# eagle_exp_2.net
KiCad netlist of a schematic drawn in EAGLE
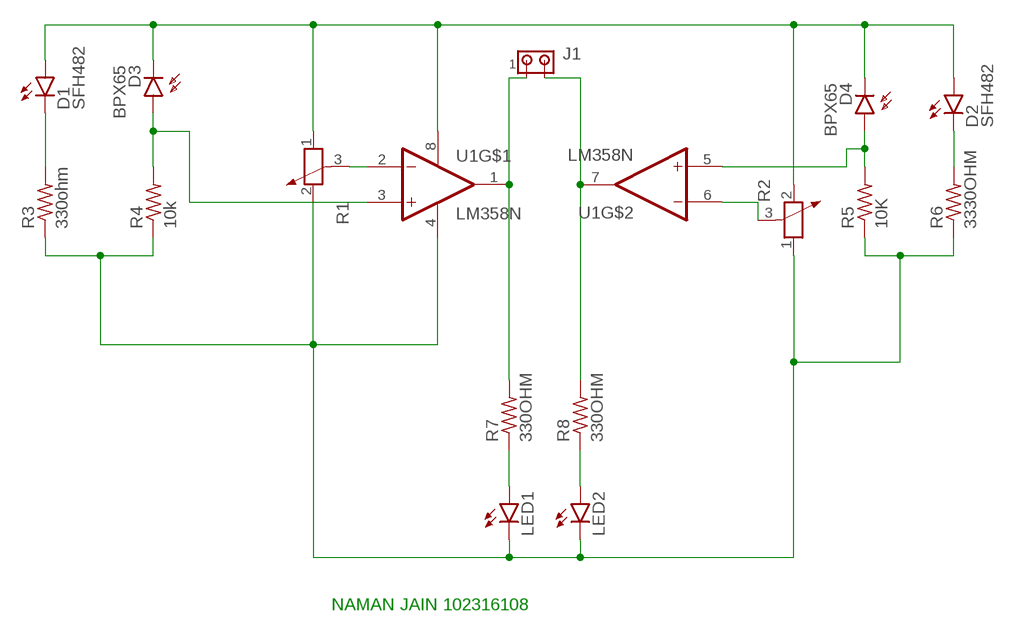
[diagram p0: schematic, sheet 1]

(export (version "E")
  (design (tool "Eeschema 10.0.6"))
  (components
    (comp (ref "D1")
      (value "SFH482")
      (footprint "eagle-import:SFH482")
      (libsource (lib "eagle-import") (part "SFH482"))
    )
    (comp (ref "D2")
      (value "SFH482")
      (footprint "eagle-import:SFH482")
      (libsource (lib "eagle-import") (part "SFH482"))
    )
    (comp (ref "D3")
      (value "BPX65")
      (footprint "eagle-import:BPX65")
      (fields (field (name "MPN") "BPX65."))
      (libsource (lib "eagle-import") (part "BPX65"))
    )
    (comp (ref "D4")
      (value "BPX65")
      (footprint "eagle-import:BPX65")
      (fields (field (name "MPN") "BPX65."))
      (libsource (lib "eagle-import") (part "BPX65"))
    )
    (comp (ref "J1")
      (value "MTA02-100")
      (footprint "eagle-import:10X02MTA")
      (libsource (lib "eagle-import") (part "MTA02-100"))
    )
    (comp (ref "LED1")
      (value "LED3MM")
      (footprint "eagle-import:LED3MM")
      (libsource (lib "eagle-import") (part "LED3MM"))
    )
    (comp (ref "LED2")
      (value "LED3MM")
      (footprint "eagle-import:LED3MM")
      (libsource (lib "eagle-import") (part "LED3MM"))
    )
    (comp (ref "R1")
      (value "POTENTIOMETER_PT-10")
      (footprint "eagle-import:PT-10")
      (libsource (lib "eagle-import") (part "POTENTIOMETER_PT-10"))
    )
    (comp (ref "R2")
      (value "POTENTIOMETER_PT-10")
      (footprint "eagle-import:PT-10")
      (libsource (lib "eagle-import") (part "POTENTIOMETER_PT-10"))
    )
    (comp (ref "R3")
      (value "330ohm")
      (footprint "eagle-import:0204_5")
      (libsource (lib "eagle-import") (part "R-US_0204/5"))
    )
    (comp (ref "R4")
      (value "10k")
      (footprint "eagle-import:0204_5")
      (libsource (lib "eagle-import") (part "R-US_0204/5"))
    )
    (comp (ref "R5")
      (value "10K")
      (footprint "eagle-import:0204_5")
      (libsource (lib "eagle-import") (part "R-US_0204/5"))
    )
    (comp (ref "R6")
      (value "3330OHM")
      (footprint "eagle-import:0204_5")
      (libsource (lib "eagle-import") (part "R-US_0204/5"))
    )
    (comp (ref "R7")
      (value "330OHM")
      (footprint "eagle-import:0204_5")
      (libsource (lib "eagle-import") (part "R-US_0204/5"))
    )
    (comp (ref "R8")
      (value "330OHM")
      (footprint "eagle-import:0204_5")
      (libsource (lib "eagle-import") (part "R-US_0204/5"))
    )
    (comp (ref "U1")
      (value "LM358N")
      (footprint "eagle-import:DIP762W46P254L960H508Q8")
      (fields (field (name "MF") "Harris Corporation"))
      (libsource (lib "eagle-import") (part "LM358N"))
    )
  )
  (nets
    (net (code "1") (name "Net-(D1-C)") (class "Default")
      (node (ref "D1") (pin "K") (pinfunction "C_K") (pintype "passive"))
      (node (ref "R3") (pin "2") (pinfunction "2_2") (pintype "passive"))
    )
    (net (code "2") (name "Net-(D2-C)") (class "Default")
      (node (ref "D2") (pin "K") (pinfunction "C_K") (pintype "passive"))
      (node (ref "R6") (pin "2") (pinfunction "2_2") (pintype "passive"))
    )
    (net (code "3") (name "Net-(D3-C)") (class "Default")
      (node (ref "D1") (pin "A") (pinfunction "A_A") (pintype "passive"))
      (node (ref "D2") (pin "A") (pinfunction "A_A") (pintype "passive"))
      (node (ref "D3") (pin "K") (pinfunction "C_K") (pintype "passive"))
      (node (ref "D4") (pin "K") (pinfunction "C_K") (pintype "passive"))
      (node (ref "R1") (pin "1") (pinfunction "1_1") (pintype "passive"))
      (node (ref "R2") (pin "2") (pinfunction "2_2") (pintype "passive"))
      (node (ref "U1") (pin "8") (pinfunction "VCC_8") (pintype "power_in"))
    )
    (net (code "4") (name "Net-(LED1-C)") (class "Default")
      (node (ref "LED1") (pin "K") (pinfunction "C_K") (pintype "passive"))
      (node (ref "LED2") (pin "K") (pinfunction "C_K") (pintype "passive"))
      (node (ref "R1") (pin "2") (pinfunction "2_2") (pintype "passive"))
      (node (ref "R2") (pin "1") (pinfunction "1_1") (pintype "passive"))
      (node (ref "R3") (pin "1") (pinfunction "1_1") (pintype "passive"))
      (node (ref "R4") (pin "1") (pinfunction "1_1") (pintype "passive"))
      (node (ref "R5") (pin "1") (pinfunction "1_1") (pintype "passive"))
      (node (ref "R6") (pin "1") (pinfunction "1_1") (pintype "passive"))
      (node (ref "U1") (pin "4") (pinfunction "GND_4") (pintype "power_in"))
    )
    (net (code "5") (name "Net-(LED1-PadA)") (class "Default")
      (node (ref "LED1") (pin "A") (pinfunction "A_A") (pintype "passive"))
      (node (ref "R7") (pin "1") (pinfunction "1_1") (pintype "passive"))
    )
    (net (code "6") (name "Net-(LED2-PadA)") (class "Default")
      (node (ref "LED2") (pin "A") (pinfunction "A_A") (pintype "passive"))
      (node (ref "R8") (pin "1") (pinfunction "1_1") (pintype "passive"))
    )
    (net (code "7") (name "Net-(U1A-1IN+)") (class "Default")
      (node (ref "D3") (pin "A") (pinfunction "A_A") (pintype "passive"))
      (node (ref "R4") (pin "2") (pinfunction "2_2") (pintype "passive"))
      (node (ref "U1") (pin "3") (pinfunction "1IN+_3") (pintype "input"))
    )
    (net (code "8") (name "Net-(U1A-1IN-)") (class "Default")
      (node (ref "R1") (pin "3") (pinfunction "3_3") (pintype "passive"))
      (node (ref "U1") (pin "2") (pinfunction "1IN-_2") (pintype "input"))
    )
    (net (code "9") (name "Net-(U1A-1OUT)") (class "Default")
      (node (ref "J1") (pin "1") (pinfunction "1_1") (pintype "passive"))
      (node (ref "R7") (pin "2") (pinfunction "2_2") (pintype "passive"))
      (node (ref "U1") (pin "1") (pinfunction "1OUT_1") (pintype "output"))
    )
    (net (code "10") (name "Net-(U1B-2IN+)") (class "Default")
      (node (ref "D4") (pin "A") (pinfunction "A_A") (pintype "passive"))
      (node (ref "R5") (pin "2") (pinfunction "2_2") (pintype "passive"))
      (node (ref "U1") (pin "5") (pinfunction "2IN+_5") (pintype "input"))
    )
    (net (code "11") (name "Net-(U1B-2IN-)") (class "Default")
      (node (ref "R2") (pin "3") (pinfunction "3_3") (pintype "passive"))
      (node (ref "U1") (pin "6") (pinfunction "2IN-_6") (pintype "input"))
    )
    (net (code "12") (name "Net-(U1B-2OUT)") (class "Default")
      (node (ref "J1") (pin "2") (pinfunction "2_2") (pintype "passive"))
      (node (ref "R8") (pin "2") (pinfunction "2_2") (pintype "passive"))
      (node (ref "U1") (pin "7") (pinfunction "2OUT_7") (pintype "output"))
    )
  )
)
